# gobabygo_motor_controller.net
KiCad netlist of a schematic drawn in EAGLE
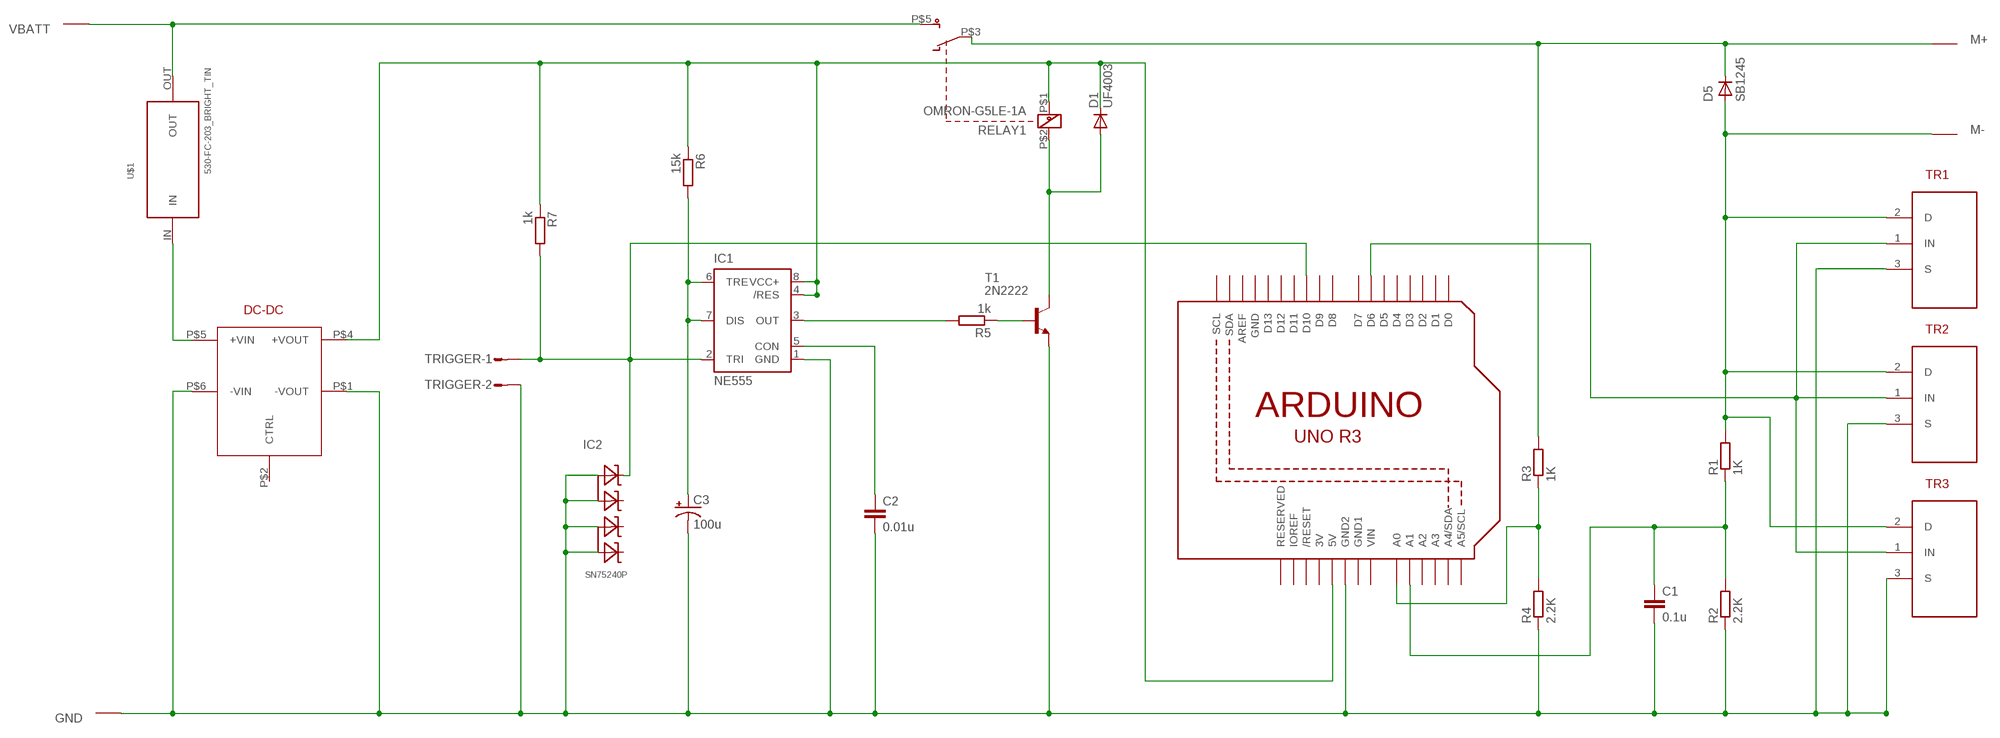
[diagram p0: schematic, sheet 1]

(export (version "E")
  (design (tool "Eeschema 10.0.6"))
  (components
    (comp (ref "ARDUINO-UNO")
      (value "ARDUINOR3-DIMENSION")
      (footprint "eagle-import:ARDUINOR3")
      (libsource (lib "eagle-import") (part "ARDUINOR3-DIMENSION"))
    )
    (comp (ref "C1")
      (value "0.1u")
      (footprint "eagle-import:C2.5-3")
      (libsource (lib "eagle-import") (part "C2,5-3"))
    )
    (comp (ref "C2")
      (value "0.01u")
      (footprint "eagle-import:C2.5-3")
      (libsource (lib "eagle-import") (part "C2,5-3"))
    )
    (comp (ref "C3")
      (value "100u")
      (footprint "eagle-import:E3,5-8")
      (libsource (lib "eagle-import") (part "CPOL-USE3.5-8"))
    )
    (comp (ref "D1")
      (value "UF4003")
      (footprint "eagle-import:DO41-10")
      (libsource (lib "eagle-import") (part "UF4003"))
    )
    (comp (ref "D5")
      (value "SB1245")
      (footprint "eagle-import:DO-201")
      (libsource (lib "eagle-import") (part "SB1245"))
    )
    (comp (ref "DC-DC")
      (value "NCS1S1205SC")
      (footprint "eagle-import:NCS1S1205SC")
      (libsource (lib "eagle-import") (part "NCS1S1205SC"))
    )
    (comp (ref "GND")
      (value "1287-ST-CONNECTOR")
      (footprint "eagle-import:F-TERMINAL")
      (libsource (lib "eagle-import") (part "1287-ST-CONNECTOR"))
    )
    (comp (ref "IC1")
      (value "NE555")
      (footprint "eagle-import:DIL-08")
      (fields (field (name "MF") "Arrow Electronics") (field (name "MPN") "NE555N"))
      (libsource (lib "eagle-import") (part "NE555"))
    )
    (comp (ref "IC2")
      (value "SN75240P")
      (footprint "eagle-import:DIL08")
      (libsource (lib "eagle-import") (part "SN75240P"))
    )
    (comp (ref "M+")
      (value "1287-ST-CONNECTOR")
      (footprint "eagle-import:F-TERMINAL")
      (libsource (lib "eagle-import") (part "1287-ST-CONNECTOR"))
    )
    (comp (ref "M-")
      (value "1287-ST-CONNECTOR")
      (footprint "eagle-import:F-TERMINAL")
      (libsource (lib "eagle-import") (part "1287-ST-CONNECTOR"))
    )
    (comp (ref "R1")
      (value "1K")
      (footprint "eagle-import:0204_7")
      (libsource (lib "eagle-import") (part "R-EU_0204/7"))
    )
    (comp (ref "R2")
      (value "2.2K")
      (footprint "eagle-import:0204_7")
      (libsource (lib "eagle-import") (part "R-EU_0204/7"))
    )
    (comp (ref "R3")
      (value "1K")
      (footprint "eagle-import:0204_7")
      (libsource (lib "eagle-import") (part "R-EU_0204/7"))
    )
    (comp (ref "R4")
      (value "2.2K")
      (footprint "eagle-import:0204_7")
      (libsource (lib "eagle-import") (part "R-EU_0204/7"))
    )
    (comp (ref "R5")
      (value "1k")
      (footprint "eagle-import:0204_7")
      (libsource (lib "eagle-import") (part "R-EU_0204/7"))
    )
    (comp (ref "R6")
      (value "15k")
      (footprint "eagle-import:0204_7")
      (libsource (lib "eagle-import") (part "R-EU_0204/7"))
    )
    (comp (ref "R7")
      (value "1k")
      (footprint "eagle-import:0204_7")
      (libsource (lib "eagle-import") (part "R-EU_0204/7"))
    )
    (comp (ref "RELAY1")
      (value "OMRON-G5LE-1A")
      (footprint "eagle-import:OMRON-G5LE-1A")
      (libsource (lib "eagle-import") (part "OMRON-G5LE-1A"))
    )
    (comp (ref "T1")
      (value "2N2222")
      (footprint "eagle-import:TO92-EBC-OVAL")
      (libsource (lib "eagle-import") (part "2N2222"))
    )
    (comp (ref "TR1")
      (value "BTS117BKSA1")
      (footprint "eagle-import:BTS117-THRU-HOLE")
      (libsource (lib "eagle-import") (part "BTS117BKSA1"))
    )
    (comp (ref "TR2")
      (value "BTS117BKSA1")
      (footprint "eagle-import:BTS117-THRU-HOLE")
      (libsource (lib "eagle-import") (part "BTS117BKSA1"))
    )
    (comp (ref "TR3")
      (value "BTS117BKSA1")
      (footprint "eagle-import:BTS117-THRU-HOLE")
      (libsource (lib "eagle-import") (part "BTS117BKSA1"))
    )
    (comp (ref "TRIGGER")
      (value "S02P")
      (footprint "eagle-import:S02P")
      (libsource (lib "eagle-import") (part "S02P"))
    )
    (comp (ref "U$1")
      (value "530-FC-203_BRIGHT_TIN")
      (footprint "eagle-import:530-FC-203-PAIR")
      (libsource (lib "eagle-import") (part "530-FC-203_BRIGHT_TIN"))
    )
    (comp (ref "VBATT")
      (value "1287-ST-CONNECTOR")
      (footprint "eagle-import:F-TERMINAL")
      (libsource (lib "eagle-import") (part "1287-ST-CONNECTOR"))
    )
  )
  (nets
    (net (code "1") (name "/3V") (class "Default")
      (node (ref "ARDUINO-UNO") (pin "3V") (pinfunction "3V_3V") (pintype "power_in"))
    )
    (net (code "2") (name "/GND") (class "Default")
      (node (ref "ARDUINO-UNO") (pin "GND") (pinfunction "GND_GND") (pintype "power_in"))
    )
    (net (code "3") (name "/GND1") (class "Default")
      (node (ref "ARDUINO-UNO") (pin "GND1") (pinfunction "GND1_GND1") (pintype "power_in"))
    )
    (net (code "4") (name "/VIN") (class "Default")
      (node (ref "ARDUINO-UNO") (pin "VIN") (pinfunction "VIN_VIN") (pintype "power_in"))
    )
    (net (code "5") (name "Net-(ARDUINO-UNO-PadA0)") (class "Default")
      (node (ref "ARDUINO-UNO") (pin "A0") (pinfunction "A0_A0") (pintype "bidirectional"))
      (node (ref "R3") (pin "1") (pinfunction "1_1") (pintype "passive"))
      (node (ref "R4") (pin "2") (pinfunction "2_2") (pintype "passive"))
    )
    (net (code "6") (name "Net-(ARDUINO-UNO-PadA1)") (class "Default")
      (node (ref "ARDUINO-UNO") (pin "A1") (pinfunction "A1_A1") (pintype "bidirectional"))
      (node (ref "C1") (pin "1") (pinfunction "1_1") (pintype "passive"))
      (node (ref "R1") (pin "1") (pinfunction "1_1") (pintype "passive"))
      (node (ref "R2") (pin "2") (pinfunction "2_2") (pintype "passive"))
    )
    (net (code "7") (name "Net-(DC-DC-+VIN)") (class "Default")
      (node (ref "DC-DC") (pin "P$5") (pinfunction "+VIN_P$5") (pintype "bidirectional"))
      (node (ref "U$1") (pin "IN") (pinfunction "IN_IN") (pintype "bidirectional"))
    )
    (net (code "8") (name "Net-(DC-DC-+VOUT)") (class "Default")
      (node (ref "ARDUINO-UNO") (pin "5V") (pinfunction "5V_5V") (pintype "power_in"))
      (node (ref "D1") (pin "C") (pinfunction "C_C") (pintype "passive"))
      (node (ref "DC-DC") (pin "P$4") (pinfunction "+VOUT_P$4") (pintype "bidirectional"))
      (node (ref "IC1") (pin "4") (pinfunction "/RES_4") (pintype "input"))
      (node (ref "IC1") (pin "8") (pinfunction "VCC+_8") (pintype "power_in"))
      (node (ref "R6") (pin "1") (pinfunction "1_1") (pintype "passive"))
      (node (ref "R7") (pin "1") (pinfunction "1_1") (pintype "passive"))
      (node (ref "RELAY1") (pin "P$1") (pinfunction "1_P$1") (pintype "passive"))
    )
    (net (code "9") (name "Net-(DC-DC--VIN)") (class "Default")
      (node (ref "ARDUINO-UNO") (pin "GND2") (pinfunction "GND2_GND2") (pintype "power_in"))
      (node (ref "C1") (pin "2") (pinfunction "2_2") (pintype "passive"))
      (node (ref "C2") (pin "2") (pinfunction "2_2") (pintype "passive"))
      (node (ref "C3") (pin "-") (pinfunction "-_-") (pintype "passive"))
      (node (ref "DC-DC") (pin "P$1") (pinfunction "-VOUT_P$1") (pintype "bidirectional"))
      (node (ref "DC-DC") (pin "P$6") (pinfunction "-VIN_P$6") (pintype "bidirectional"))
      (node (ref "GND") (pin "P$1") (pinfunction "P$1_P$1") (pintype "bidirectional"))
      (node (ref "IC1") (pin "1") (pinfunction "GND_1") (pintype "power_in"))
      (node (ref "IC2") (pin "1") (pinfunction "A4_1") (pintype "passive"))
      (node (ref "IC2") (pin "3") (pinfunction "A3_3") (pintype "passive"))
      (node (ref "IC2") (pin "5") (pinfunction "A2_5") (pintype "passive"))
      (node (ref "IC2") (pin "7") (pinfunction "A1_7") (pintype "passive"))
      (node (ref "R2") (pin "1") (pinfunction "1_1") (pintype "passive"))
      (node (ref "R4") (pin "1") (pinfunction "1_1") (pintype "passive"))
      (node (ref "T1") (pin "E") (pinfunction "E_E") (pintype "passive"))
      (node (ref "TR1") (pin "3") (pinfunction "S_3") (pintype "bidirectional"))
      (node (ref "TR2") (pin "3") (pinfunction "S_3") (pintype "bidirectional"))
      (node (ref "TR3") (pin "3") (pinfunction "S_3") (pintype "bidirectional"))
      (node (ref "TRIGGER") (pin "2") (pinfunction "S_2") (pintype "passive"))
    )
    (net (code "10") (name "Net-(IC1-CON)") (class "Default")
      (node (ref "C2") (pin "1") (pinfunction "1_1") (pintype "passive"))
      (node (ref "IC1") (pin "5") (pinfunction "CON_5") (pintype "input"))
    )
    (net (code "11") (name "Net-(IC1-DIS)") (class "Default")
      (node (ref "C3") (pin "+") (pinfunction "+_+") (pintype "passive"))
      (node (ref "IC1") (pin "6") (pinfunction "TRE_6") (pintype "input"))
      (node (ref "IC1") (pin "7") (pinfunction "DIS_7") (pintype "input"))
      (node (ref "R6") (pin "2") (pinfunction "2_2") (pintype "passive"))
    )
    (net (code "12") (name "Net-(IC1-OUT)") (class "Default")
      (node (ref "IC1") (pin "3") (pinfunction "OUT_3") (pintype "output"))
      (node (ref "R5") (pin "2") (pinfunction "2_2") (pintype "passive"))
    )
    (net (code "13") (name "Net-(IC1-TRI)") (class "Default")
      (node (ref "ARDUINO-UNO") (pin "D10") (pinfunction "D10_D10") (pintype "bidirectional"))
      (node (ref "IC1") (pin "2") (pinfunction "TRI_2") (pintype "input"))
      (node (ref "IC2") (pin "8") (pinfunction "C1_8") (pintype "passive"))
      (node (ref "R7") (pin "2") (pinfunction "2_2") (pintype "passive"))
      (node (ref "TRIGGER") (pin "1") (pinfunction "S_1") (pintype "passive"))
    )
    (net (code "14") (name "Net-(R5-Pad1)") (class "Default")
      (node (ref "R5") (pin "1") (pinfunction "1_1") (pintype "passive"))
      (node (ref "T1") (pin "B") (pinfunction "B_B") (pintype "passive"))
    )
    (net (code "15") (name "Net-(RELAY1-2)") (class "Default")
      (node (ref "D1") (pin "A") (pinfunction "A_A") (pintype "passive"))
      (node (ref "RELAY1") (pin "P$2") (pinfunction "2_P$2") (pintype "passive"))
      (node (ref "T1") (pin "C") (pinfunction "C_C") (pintype "passive"))
    )
    (net (code "16") (name "Net-(RELAY1-5)") (class "Default")
      (node (ref "D5") (pin "C") (pinfunction "C_C") (pintype "passive"))
      (node (ref "M+") (pin "P$1") (pinfunction "P$1_P$1") (pintype "bidirectional"))
      (node (ref "R3") (pin "2") (pinfunction "2_2") (pintype "passive"))
      (node (ref "RELAY1") (pin "P$3") (pinfunction "5_P$3") (pintype "passive"))
    )
    (net (code "17") (name "Net-(RELAY1-6)") (class "Default")
      (node (ref "RELAY1") (pin "P$5") (pinfunction "6_P$5") (pintype "passive"))
      (node (ref "U$1") (pin "OUT") (pinfunction "OUT_OUT") (pintype "bidirectional"))
      (node (ref "VBATT") (pin "P$1") (pinfunction "P$1_P$1") (pintype "bidirectional"))
    )
    (net (code "18") (name "Net-(TR1-D)") (class "Default")
      (node (ref "D5") (pin "A") (pinfunction "A_A") (pintype "passive"))
      (node (ref "M-") (pin "P$1") (pinfunction "P$1_P$1") (pintype "bidirectional"))
      (node (ref "R1") (pin "2") (pinfunction "2_2") (pintype "passive"))
      (node (ref "TR1") (pin "2") (pinfunction "D_2") (pintype "bidirectional"))
      (node (ref "TR2") (pin "2") (pinfunction "D_2") (pintype "bidirectional"))
      (node (ref "TR3") (pin "2") (pinfunction "D_2") (pintype "bidirectional"))
    )
    (net (code "19") (name "Net-(TR1-IN)") (class "Default")
      (node (ref "ARDUINO-UNO") (pin "D6") (pinfunction "D6_D6") (pintype "bidirectional"))
      (node (ref "TR1") (pin "1") (pinfunction "IN_1") (pintype "bidirectional"))
      (node (ref "TR2") (pin "1") (pinfunction "IN_1") (pintype "bidirectional"))
      (node (ref "TR3") (pin "1") (pinfunction "IN_1") (pintype "bidirectional"))
    )
    (net (code "20") (name "unconnected-(ARDUINO-UNO-A4{slash}SDA-PadA4)") (class "Default")
      (node (ref "ARDUINO-UNO") (pin "A4") (pinfunction "A4/SDA_A4") (pintype "bidirectional"))
    )
    (net (code "21") (name "unconnected-(ARDUINO-UNO-A5{slash}SCL-PadA5)") (class "Default")
      (node (ref "ARDUINO-UNO") (pin "A5") (pinfunction "A5/SCL_A5") (pintype "bidirectional"))
    )
    (net (code "22") (name "unconnected-(ARDUINO-UNO-PadA2)") (class "Default")
      (node (ref "ARDUINO-UNO") (pin "A2") (pinfunction "A2_A2") (pintype "bidirectional"))
    )
    (net (code "23") (name "unconnected-(ARDUINO-UNO-PadA3)") (class "Default")
      (node (ref "ARDUINO-UNO") (pin "A3") (pinfunction "A3_A3") (pintype "bidirectional"))
    )
    (net (code "24") (name "unconnected-(ARDUINO-UNO-PadAREF)") (class "Default")
      (node (ref "ARDUINO-UNO") (pin "AREF") (pinfunction "AREF_AREF") (pintype "bidirectional"))
    )
    (net (code "25") (name "unconnected-(ARDUINO-UNO-PadD0)") (class "Default")
      (node (ref "ARDUINO-UNO") (pin "D0") (pinfunction "D0_D0") (pintype "bidirectional"))
    )
    (net (code "26") (name "unconnected-(ARDUINO-UNO-PadD1)") (class "Default")
      (node (ref "ARDUINO-UNO") (pin "D1") (pinfunction "D1_D1") (pintype "bidirectional"))
    )
    (net (code "27") (name "unconnected-(ARDUINO-UNO-PadD2)") (class "Default")
      (node (ref "ARDUINO-UNO") (pin "D2") (pinfunction "D2_D2") (pintype "bidirectional"))
    )
    (net (code "28") (name "unconnected-(ARDUINO-UNO-PadD3)") (class "Default")
      (node (ref "ARDUINO-UNO") (pin "D3") (pinfunction "D3_D3") (pintype "bidirectional"))
    )
    (net (code "29") (name "unconnected-(ARDUINO-UNO-PadD4)") (class "Default")
      (node (ref "ARDUINO-UNO") (pin "D4") (pinfunction "D4_D4") (pintype "bidirectional"))
    )
    (net (code "30") (name "unconnected-(ARDUINO-UNO-PadD5)") (class "Default")
      (node (ref "ARDUINO-UNO") (pin "D5") (pinfunction "D5_D5") (pintype "bidirectional"))
    )
    (net (code "31") (name "unconnected-(ARDUINO-UNO-PadD7)") (class "Default")
      (node (ref "ARDUINO-UNO") (pin "D7") (pinfunction "D7_D7") (pintype "bidirectional"))
    )
    (net (code "32") (name "unconnected-(ARDUINO-UNO-PadD8)") (class "Default")
      (node (ref "ARDUINO-UNO") (pin "D8") (pinfunction "D8_D8") (pintype "bidirectional"))
    )
    (net (code "33") (name "unconnected-(ARDUINO-UNO-PadD9)") (class "Default")
      (node (ref "ARDUINO-UNO") (pin "D9") (pinfunction "D9_D9") (pintype "bidirectional"))
    )
    (net (code "34") (name "unconnected-(ARDUINO-UNO-PadD11)") (class "Default")
      (node (ref "ARDUINO-UNO") (pin "D11") (pinfunction "D11_D11") (pintype "bidirectional"))
    )
    (net (code "35") (name "unconnected-(ARDUINO-UNO-PadD12)") (class "Default")
      (node (ref "ARDUINO-UNO") (pin "D12") (pinfunction "D12_D12") (pintype "bidirectional"))
    )
    (net (code "36") (name "unconnected-(ARDUINO-UNO-PadD13)") (class "Default")
      (node (ref "ARDUINO-UNO") (pin "D13") (pinfunction "D13_D13") (pintype "bidirectional"))
    )
    (net (code "37") (name "unconnected-(ARDUINO-UNO-PadIOREF)") (class "Default")
      (node (ref "ARDUINO-UNO") (pin "IOREF") (pinfunction "IOREF_IOREF") (pintype "output"))
    )
    (net (code "38") (name "unconnected-(ARDUINO-UNO-PadRESERVED)") (class "Default")
      (node (ref "ARDUINO-UNO") (pin "RESERVED") (pinfunction "RESERVED_RESERVED") (pintype "no_connect"))
    )
    (net (code "39") (name "unconnected-(ARDUINO-UNO-PadSCL)") (class "Default")
      (node (ref "ARDUINO-UNO") (pin "SCL") (pinfunction "SCL_SCL") (pintype "bidirectional"))
    )
    (net (code "40") (name "unconnected-(ARDUINO-UNO-PadSDA)") (class "Default")
      (node (ref "ARDUINO-UNO") (pin "SDA") (pinfunction "SDA_SDA") (pintype "bidirectional"))
    )
    (net (code "41") (name "unconnected-(ARDUINO-UNO-{slash}RESET-PadRESET)") (class "Default")
      (node (ref "ARDUINO-UNO") (pin "RESET") (pinfunction "/RESET_RESET") (pintype "bidirectional"))
    )
    (net (code "42") (name "unconnected-(DC-DC-CTRL-PadP$2)") (class "Default")
      (node (ref "DC-DC") (pin "P$2") (pinfunction "CTRL_P$2") (pintype "bidirectional"))
    )
    (net (code "43") (name "unconnected-(IC2-C2-Pad6)") (class "Default")
      (node (ref "IC2") (pin "6") (pinfunction "C2_6") (pintype "passive"))
    )
    (net (code "44") (name "unconnected-(IC2-C3-Pad4)") (class "Default")
      (node (ref "IC2") (pin "4") (pinfunction "C3_4") (pintype "passive"))
    )
    (net (code "45") (name "unconnected-(IC2-C4-Pad2)") (class "Default")
      (node (ref "IC2") (pin "2") (pinfunction "C4_2") (pintype "passive"))
    )
  )
)
